# CAN_5V.net
KiCad netlist of a schematic drawn in Altium Designer
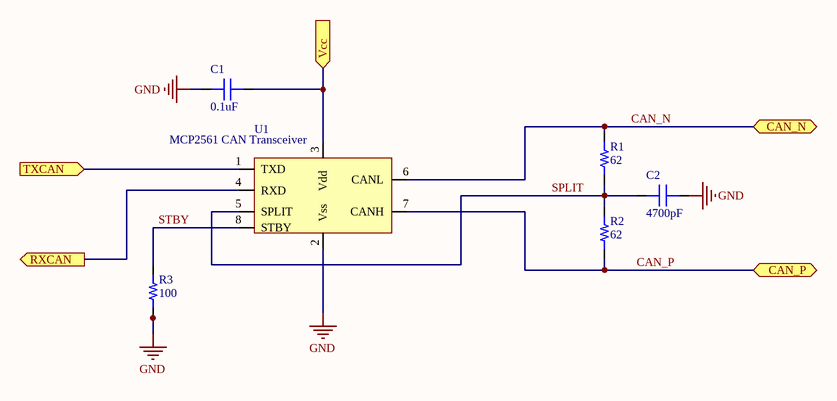
[diagram p0: CAN_5V.SchDoc]

(export (version "E")
  (design (tool "Eeschema 10.0.6"))
  (components
    (comp (ref "C1")
      (value "capacitor")
      (footprint "0603")
      (description "Generic 0603 capacitor")
      (fields (field (name "CAPACITANCE") "0.1uF") (field (name "VOLTAGE") "50"))
      (libsource (lib "altlib") (part "capacitor"))
    )
    (comp (ref "C2")
      (value "capacitor")
      (footprint "0603")
      (description "Generic 0603 capacitor")
      (fields (field (name "CAPACITANCE") "4700pF") (field (name "VOLTAGE") "50"))
      (libsource (lib "altlib") (part "capacitor"))
    )
    (comp (ref "R1")
      (value "62")
      (footprint "RES 0603/1608")
      (fields (field (name "RESISTANCE") "62"))
      (libsource (lib "altlib") (part "Resistor"))
    )
    (comp (ref "R2")
      (value "62")
      (footprint "RES 0603/1608")
      (fields (field (name "RESISTANCE") "62"))
      (libsource (lib "altlib") (part "Resistor"))
    )
    (comp (ref "R3")
      (value "100")
      (footprint "RES 0603/1608")
      (fields (field (name "RESISTANCE") "100"))
      (libsource (lib "altlib") (part "Resistor"))
    )
    (comp (ref "U1")
      (value "MCP2561 CAN Transceiver")
      (footprint "SOIC-8")
      (libsource (lib "altlib") (part "MCP2561 CAN Transceiver"))
    )
  )
  (nets
    (net (code "1") (name "/CAN_N") (class "Default")
      (node (ref "R1") (pin "2") (pinfunction "2_2") (pintype "passive"))
      (node (ref "U1") (pin "6") (pinfunction "CANL_6") (pintype "passive"))
    )
    (net (code "2") (name "/CAN_P") (class "Default")
      (node (ref "R2") (pin "1") (pinfunction "1_1") (pintype "passive"))
      (node (ref "U1") (pin "7") (pinfunction "CANH_7") (pintype "passive"))
    )
    (net (code "3") (name "/RXCAN") (class "Default")
      (node (ref "U1") (pin "4") (pinfunction "RXD_4") (pintype "passive"))
    )
    (net (code "4") (name "/SPLIT") (class "Default")
      (node (ref "C2") (pin "1") (pinfunction "1_1") (pintype "passive"))
      (node (ref "R1") (pin "1") (pinfunction "1_1") (pintype "passive"))
      (node (ref "R2") (pin "2") (pinfunction "2_2") (pintype "passive"))
      (node (ref "U1") (pin "5") (pinfunction "SPLIT_5") (pintype "passive"))
    )
    (net (code "5") (name "/STBY") (class "Default")
      (node (ref "R3") (pin "2") (pinfunction "2_2") (pintype "passive"))
      (node (ref "U1") (pin "8") (pinfunction "STBY_8") (pintype "passive"))
    )
    (net (code "6") (name "/TXCAN") (class "Default")
      (node (ref "U1") (pin "1") (pinfunction "TXD_1") (pintype "passive"))
    )
    (net (code "7") (name "/Vcc") (class "Default")
      (node (ref "C1") (pin "2") (pinfunction "2_2") (pintype "passive"))
      (node (ref "U1") (pin "3") (pinfunction "Vdd_3") (pintype "passive"))
    )
    (net (code "8") (name "GND") (class "Default")
      (node (ref "C1") (pin "1") (pinfunction "1_1") (pintype "passive"))
      (node (ref "C2") (pin "2") (pinfunction "2_2") (pintype "passive"))
      (node (ref "R3") (pin "1") (pinfunction "1_1") (pintype "passive"))
      (node (ref "U1") (pin "2") (pinfunction "Vss_2") (pintype "passive"))
    )
  )
)
